# EL_SCH.net
KiCad netlist of a schematic drawn in Altium Designer
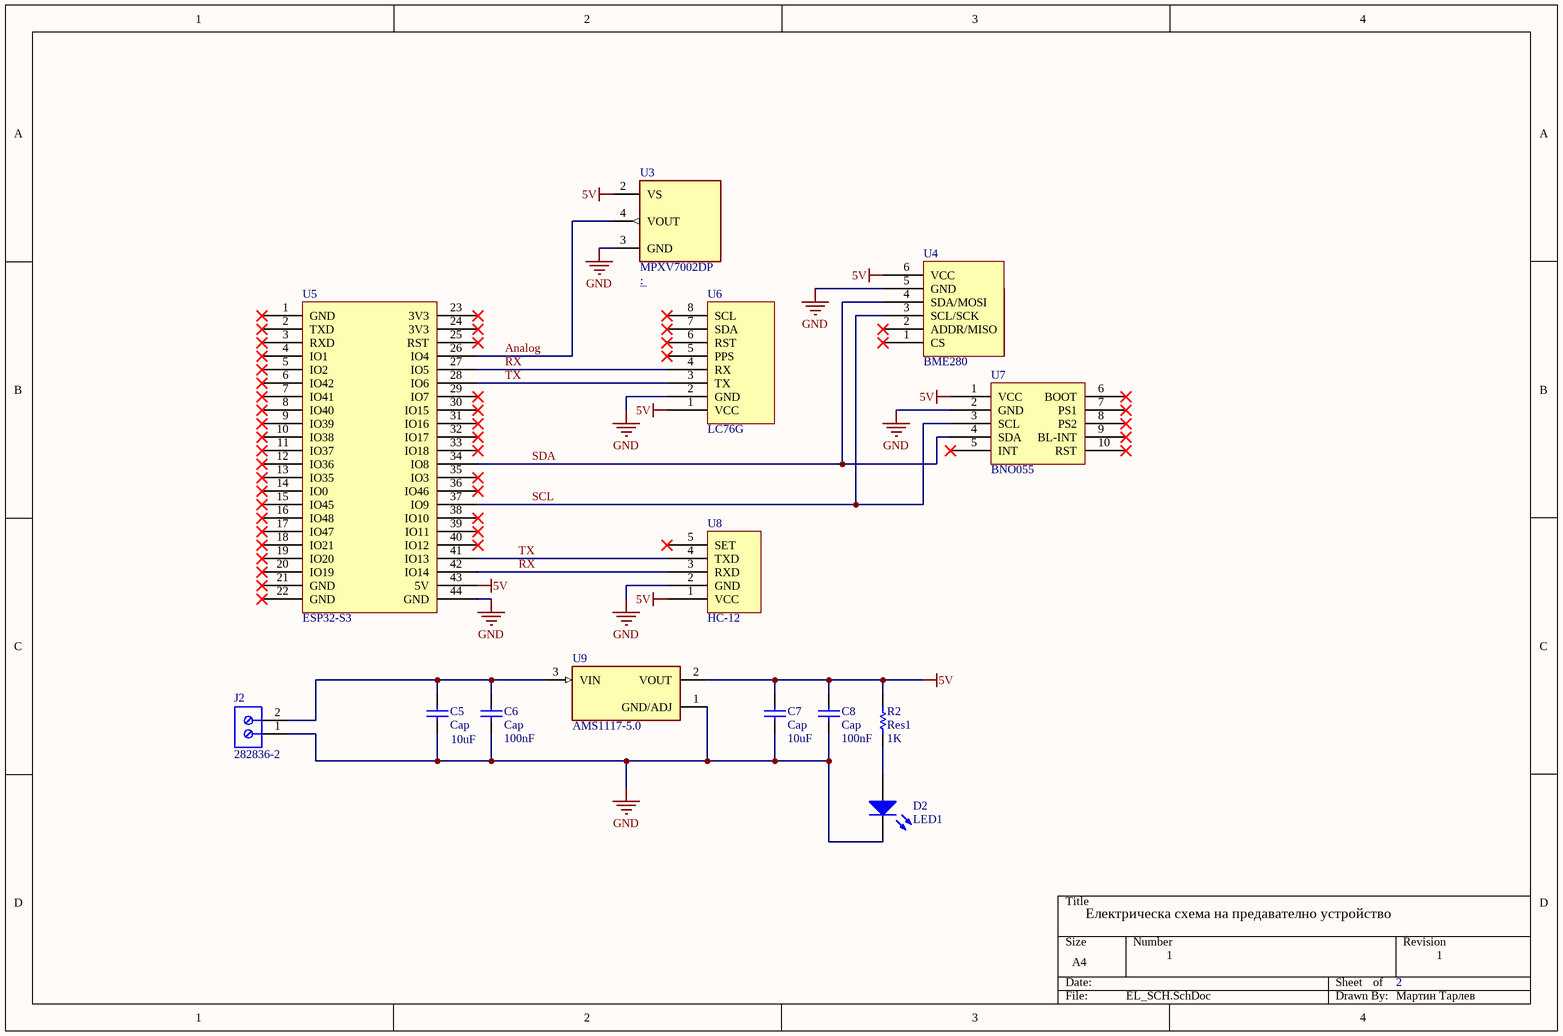
[diagram p0: EL_SCH.SchDoc]

(export (version "E")
  (design (tool "Eeschema 10.0.6"))
  (components
    (comp (ref "C5")
      (value "Cap")
      (footprint "CAP2")
      (description "Capacitor")
      (fields (field (name "ALTIUM_VALUE") "10uF") (field (name "PUBLISHER") "Altium Limited"))
      (libsource (lib "Miscellaneous Devices") (part "Cap"))
    )
    (comp (ref "C6")
      (value "Cap")
      (footprint "CON")
      (description "Capacitor")
      (fields (field (name "ALTIUM_VALUE") "100nF") (field (name "PUBLISHER") "Altium Limited"))
      (libsource (lib "Miscellaneous Devices") (part "Cap"))
    )
    (comp (ref "C7")
      (value "Cap")
      (footprint "CAP2")
      (description "Capacitor")
      (fields (field (name "ALTIUM_VALUE") "10uF") (field (name "PUBLISHER") "Altium Limited"))
      (libsource (lib "Miscellaneous Devices") (part "Cap"))
    )
    (comp (ref "C8")
      (value "Cap")
      (footprint "CON")
      (description "Capacitor")
      (fields (field (name "ALTIUM_VALUE") "100nF") (field (name "PUBLISHER") "Altium Limited"))
      (libsource (lib "Miscellaneous Devices") (part "Cap"))
    )
    (comp (ref "D2")
      (value "LED1")
      (footprint "LED-1")
      (description "Typical RED GaAs LED")
      (fields (field (name "PUBLISHER") "Altium Limited"))
      (libsource (lib "Miscellaneous Devices") (part "LED1"))
    )
    (comp (ref "J2")
      (value "282836-2")
      (footprint "TECO-282836-2_V")
      (description "Female Header, Pitch 5 mm, 1 x 2 Position, Height 10 mm, Tail Length 3.5 mm, Rohs, Bulk")
      (fields (field (name "VOLTAGE") "300V") (field (name "MANUFACTURER") "TE Connectivity"))
      (libsource (lib "Altium Content Vault") (part "CN-1P-F-TB2"))
    )
    (comp (ref "R2")
      (value "Res1")
      (footprint "AXIAL-0.3")
      (description "Resistor")
      (fields (field (name "ALTIUM_VALUE") "1K") (field (name "PUBLISHER") "Altium Limited"))
      (libsource (lib "Miscellaneous Devices") (part "Res1"))
    )
    (comp (ref "U3")
      (value "MPXV7002DP")
      (footprint "XDCR_MPXV7002DP")
      (fields (field (name "MF") "NXP USA"))
      (libsource (lib "MPXV7002DP") (part "MPXV7002DP"))
    )
    (comp (ref "U4") (value "BME280") (libsource (lib "First_PCB_dip") (part "BME280")))
    (comp (ref "U5") (value "ESP32-S3") (libsource (lib "First_PCB_dip") (part "ESP32-S3")))
    (comp (ref "U6") (value "LC76G") (libsource (lib "First_PCB_dip") (part "LC76G")))
    (comp (ref "U7") (value "BNO055") (libsource (lib "First_PCB_dip") (part "BNO055")))
    (comp (ref "U8") (value "HC-12") (libsource (lib "First_PCB_dip") (part "HC-12")))
    (comp (ref "U9")
      (value "AMS1117-5.0")
      (footprint "SOT229P700X180-4N")
      (description "1A LOW DROPOUT VOLTAGE REGULATOR")
      (fields (field (name "MF") "ams"))
      (libsource (lib "AMS1117-5.0") (part "AMS1117-5.0"))
    )
  )
  (nets
    (net (code "1") (name "/Analog") (class "Default")
      (node (ref "U3") (pin "4") (pinfunction "VOUT_4") (pintype "output"))
      (node (ref "U5") (pin "26") (pinfunction "IO4_26") (pintype "passive"))
    )
    (net (code "2") (name "/RX") (class "Default")
      (node (ref "U5") (pin "27") (pinfunction "IO5_27") (pintype "passive"))
      (node (ref "U5") (pin "42") (pinfunction "IO14_42") (pintype "passive"))
      (node (ref "U6") (pin "4") (pinfunction "RX_4") (pintype "passive"))
      (node (ref "U8") (pin "3") (pinfunction "RXD_3") (pintype "passive"))
    )
    (net (code "3") (name "/SCL") (class "Default")
      (node (ref "U4") (pin "3") (pinfunction "SCL/SCK_3") (pintype "passive"))
      (node (ref "U5") (pin "37") (pinfunction "IO9_37") (pintype "passive"))
      (node (ref "U7") (pin "3") (pinfunction "SCL_3") (pintype "passive"))
    )
    (net (code "4") (name "/SDA") (class "Default")
      (node (ref "U4") (pin "4") (pinfunction "SDA/MOSI_4") (pintype "passive"))
      (node (ref "U5") (pin "34") (pinfunction "IO8_34") (pintype "passive"))
      (node (ref "U7") (pin "4") (pinfunction "SDA_4") (pintype "passive"))
    )
    (net (code "5") (name "/TX") (class "Default")
      (node (ref "U5") (pin "28") (pinfunction "IO6_28") (pintype "passive"))
      (node (ref "U5") (pin "41") (pinfunction "IO13_41") (pintype "passive"))
      (node (ref "U6") (pin "3") (pinfunction "TX_3") (pintype "passive"))
      (node (ref "U8") (pin "4") (pinfunction "TXD_4") (pintype "passive"))
    )
    (net (code "6") (name "5V") (class "Default")
      (node (ref "C7") (pin "2") (pinfunction "2_2") (pintype "passive"))
      (node (ref "C8") (pin "2") (pinfunction "2_2") (pintype "passive"))
      (node (ref "R2") (pin "2") (pinfunction "2_2") (pintype "passive"))
      (node (ref "U3") (pin "2") (pinfunction "VS_2") (pintype "power_in"))
      (node (ref "U4") (pin "6") (pinfunction "VCC_6") (pintype "passive"))
      (node (ref "U5") (pin "43") (pinfunction "5V_43") (pintype "passive"))
      (node (ref "U6") (pin "1") (pinfunction "VCC_1") (pintype "passive"))
      (node (ref "U7") (pin "1") (pinfunction "VCC_1") (pintype "passive"))
      (node (ref "U8") (pin "1") (pinfunction "VCC_1") (pintype "passive"))
      (node (ref "U9") (pin "2") (pinfunction "VOUT_2") (pintype "passive"))
    )
    (net (code "7") (name "GND") (class "Default")
      (node (ref "C5") (pin "1") (pinfunction "1_1") (pintype "passive"))
      (node (ref "C6") (pin "1") (pinfunction "1_1") (pintype "passive"))
      (node (ref "C7") (pin "1") (pinfunction "1_1") (pintype "passive"))
      (node (ref "C8") (pin "1") (pinfunction "1_1") (pintype "passive"))
      (node (ref "D2") (pin "2") (pinfunction "K_2") (pintype "passive"))
      (node (ref "J2") (pin "1") (pinfunction "1_1") (pintype "passive"))
      (node (ref "U3") (pin "3") (pinfunction "GND_3") (pintype "power_in"))
      (node (ref "U4") (pin "5") (pinfunction "GND_5") (pintype "passive"))
      (node (ref "U5") (pin "44") (pinfunction "GND_44") (pintype "passive"))
      (node (ref "U6") (pin "2") (pinfunction "GND_2") (pintype "passive"))
      (node (ref "U7") (pin "2") (pinfunction "GND_2") (pintype "passive"))
      (node (ref "U8") (pin "2") (pinfunction "GND_2") (pintype "passive"))
      (node (ref "U9") (pin "1") (pinfunction "GND/ADJ_1") (pintype "power_in"))
    )
    (net (code "8") (name "Net-(D2-A)") (class "Default")
      (node (ref "D2") (pin "1") (pinfunction "A_1") (pintype "passive"))
      (node (ref "R2") (pin "1") (pinfunction "1_1") (pintype "passive"))
    )
    (net (code "9") (name "Net-(U9-VIN)") (class "Default")
      (node (ref "C5") (pin "2") (pinfunction "2_2") (pintype "passive"))
      (node (ref "C6") (pin "2") (pinfunction "2_2") (pintype "passive"))
      (node (ref "J2") (pin "2") (pinfunction "2_2") (pintype "passive"))
      (node (ref "U9") (pin "3") (pinfunction "VIN_3") (pintype "input"))
    )
    (net (code "10") (name "unconnected-(U4-ADDR{slash}MISO-Pad2)") (class "Default")
      (node (ref "U4") (pin "2") (pinfunction "ADDR/MISO_2") (pintype "passive+no_connect"))
    )
    (net (code "11") (name "unconnected-(U4-CS-Pad1)") (class "Default")
      (node (ref "U4") (pin "1") (pinfunction "CS_1") (pintype "passive+no_connect"))
    )
    (net (code "12") (name "unconnected-(U5-3V3-Pad23)") (class "Default")
      (node (ref "U5") (pin "23") (pinfunction "3V3_23") (pintype "passive+no_connect"))
    )
    (net (code "13") (name "unconnected-(U5-3V3-Pad24)") (class "Default")
      (node (ref "U5") (pin "24") (pinfunction "3V3_24") (pintype "passive+no_connect"))
    )
    (net (code "14") (name "unconnected-(U5-GND-Pad1)") (class "Default")
      (node (ref "U5") (pin "1") (pinfunction "GND_1") (pintype "passive+no_connect"))
    )
    (net (code "15") (name "unconnected-(U5-GND-Pad21)") (class "Default")
      (node (ref "U5") (pin "21") (pinfunction "GND_21") (pintype "passive+no_connect"))
    )
    (net (code "16") (name "unconnected-(U5-GND-Pad22)") (class "Default")
      (node (ref "U5") (pin "22") (pinfunction "GND_22") (pintype "passive+no_connect"))
    )
    (net (code "17") (name "unconnected-(U5-IO0-Pad14)") (class "Default")
      (node (ref "U5") (pin "14") (pinfunction "IO0_14") (pintype "passive+no_connect"))
    )
    (net (code "18") (name "unconnected-(U5-IO1-Pad4)") (class "Default")
      (node (ref "U5") (pin "4") (pinfunction "IO1_4") (pintype "passive+no_connect"))
    )
    (net (code "19") (name "unconnected-(U5-IO2-Pad5)") (class "Default")
      (node (ref "U5") (pin "5") (pinfunction "IO2_5") (pintype "passive+no_connect"))
    )
    (net (code "20") (name "unconnected-(U5-IO3-Pad35)") (class "Default")
      (node (ref "U5") (pin "35") (pinfunction "IO3_35") (pintype "passive+no_connect"))
    )
    (net (code "21") (name "unconnected-(U5-IO7-Pad29)") (class "Default")
      (node (ref "U5") (pin "29") (pinfunction "IO7_29") (pintype "passive+no_connect"))
    )
    (net (code "22") (name "unconnected-(U5-IO10-Pad38)") (class "Default")
      (node (ref "U5") (pin "38") (pinfunction "IO10_38") (pintype "passive+no_connect"))
    )
    (net (code "23") (name "unconnected-(U5-IO11-Pad39)") (class "Default")
      (node (ref "U5") (pin "39") (pinfunction "IO11_39") (pintype "passive+no_connect"))
    )
    (net (code "24") (name "unconnected-(U5-IO12-Pad40)") (class "Default")
      (node (ref "U5") (pin "40") (pinfunction "IO12_40") (pintype "passive+no_connect"))
    )
    (net (code "25") (name "unconnected-(U5-IO15-Pad30)") (class "Default")
      (node (ref "U5") (pin "30") (pinfunction "IO15_30") (pintype "passive+no_connect"))
    )
    (net (code "26") (name "unconnected-(U5-IO16-Pad31)") (class "Default")
      (node (ref "U5") (pin "31") (pinfunction "IO16_31") (pintype "passive+no_connect"))
    )
    (net (code "27") (name "unconnected-(U5-IO17-Pad32)") (class "Default")
      (node (ref "U5") (pin "32") (pinfunction "IO17_32") (pintype "passive+no_connect"))
    )
    (net (code "28") (name "unconnected-(U5-IO18-Pad33)") (class "Default")
      (node (ref "U5") (pin "33") (pinfunction "IO18_33") (pintype "passive+no_connect"))
    )
    (net (code "29") (name "unconnected-(U5-IO19-Pad20)") (class "Default")
      (node (ref "U5") (pin "20") (pinfunction "IO19_20") (pintype "passive+no_connect"))
    )
    (net (code "30") (name "unconnected-(U5-IO20-Pad19)") (class "Default")
      (node (ref "U5") (pin "19") (pinfunction "IO20_19") (pintype "passive+no_connect"))
    )
    (net (code "31") (name "unconnected-(U5-IO21-Pad18)") (class "Default")
      (node (ref "U5") (pin "18") (pinfunction "IO21_18") (pintype "passive+no_connect"))
    )
    (net (code "32") (name "unconnected-(U5-IO35-Pad13)") (class "Default")
      (node (ref "U5") (pin "13") (pinfunction "IO35_13") (pintype "passive+no_connect"))
    )
    (net (code "33") (name "unconnected-(U5-IO36-Pad12)") (class "Default")
      (node (ref "U5") (pin "12") (pinfunction "IO36_12") (pintype "passive+no_connect"))
    )
    (net (code "34") (name "unconnected-(U5-IO37-Pad11)") (class "Default")
      (node (ref "U5") (pin "11") (pinfunction "IO37_11") (pintype "passive+no_connect"))
    )
    (net (code "35") (name "unconnected-(U5-IO38-Pad10)") (class "Default")
      (node (ref "U5") (pin "10") (pinfunction "IO38_10") (pintype "passive+no_connect"))
    )
    (net (code "36") (name "unconnected-(U5-IO39-Pad9)") (class "Default")
      (node (ref "U5") (pin "9") (pinfunction "IO39_9") (pintype "passive+no_connect"))
    )
    (net (code "37") (name "unconnected-(U5-IO40-Pad8)") (class "Default")
      (node (ref "U5") (pin "8") (pinfunction "IO40_8") (pintype "passive+no_connect"))
    )
    (net (code "38") (name "unconnected-(U5-IO41-Pad7)") (class "Default")
      (node (ref "U5") (pin "7") (pinfunction "IO41_7") (pintype "passive+no_connect"))
    )
    (net (code "39") (name "unconnected-(U5-IO42-Pad6)") (class "Default")
      (node (ref "U5") (pin "6") (pinfunction "IO42_6") (pintype "passive+no_connect"))
    )
    (net (code "40") (name "unconnected-(U5-IO45-Pad15)") (class "Default")
      (node (ref "U5") (pin "15") (pinfunction "IO45_15") (pintype "passive+no_connect"))
    )
    (net (code "41") (name "unconnected-(U5-IO46-Pad36)") (class "Default")
      (node (ref "U5") (pin "36") (pinfunction "IO46_36") (pintype "passive+no_connect"))
    )
    (net (code "42") (name "unconnected-(U5-IO47-Pad17)") (class "Default")
      (node (ref "U5") (pin "17") (pinfunction "IO47_17") (pintype "passive+no_connect"))
    )
    (net (code "43") (name "unconnected-(U5-IO48-Pad16)") (class "Default")
      (node (ref "U5") (pin "16") (pinfunction "IO48_16") (pintype "passive+no_connect"))
    )
    (net (code "44") (name "unconnected-(U5-RST-Pad25)") (class "Default")
      (node (ref "U5") (pin "25") (pinfunction "RST_25") (pintype "passive+no_connect"))
    )
    (net (code "45") (name "unconnected-(U5-RXD-Pad3)") (class "Default")
      (node (ref "U5") (pin "3") (pinfunction "RXD_3") (pintype "passive+no_connect"))
    )
    (net (code "46") (name "unconnected-(U5-TXD-Pad2)") (class "Default")
      (node (ref "U5") (pin "2") (pinfunction "TXD_2") (pintype "passive+no_connect"))
    )
    (net (code "47") (name "unconnected-(U6-PPS-Pad5)") (class "Default")
      (node (ref "U6") (pin "5") (pinfunction "PPS_5") (pintype "passive+no_connect"))
    )
    (net (code "48") (name "unconnected-(U6-RST-Pad6)") (class "Default")
      (node (ref "U6") (pin "6") (pinfunction "RST_6") (pintype "passive+no_connect"))
    )
    (net (code "49") (name "unconnected-(U6-SCL-Pad8)") (class "Default")
      (node (ref "U6") (pin "8") (pinfunction "SCL_8") (pintype "passive+no_connect"))
    )
    (net (code "50") (name "unconnected-(U6-SDA-Pad7)") (class "Default")
      (node (ref "U6") (pin "7") (pinfunction "SDA_7") (pintype "passive+no_connect"))
    )
    (net (code "51") (name "unconnected-(U7-BL-INT-Pad9)") (class "Default")
      (node (ref "U7") (pin "9") (pinfunction "BL-INT_9") (pintype "passive+no_connect"))
    )
    (net (code "52") (name "unconnected-(U7-BOOT-Pad6)") (class "Default")
      (node (ref "U7") (pin "6") (pinfunction "BOOT_6") (pintype "passive+no_connect"))
    )
    (net (code "53") (name "unconnected-(U7-INT-Pad5)") (class "Default")
      (node (ref "U7") (pin "5") (pinfunction "INT_5") (pintype "passive+no_connect"))
    )
    (net (code "54") (name "unconnected-(U7-PS1-Pad7)") (class "Default")
      (node (ref "U7") (pin "7") (pinfunction "PS1_7") (pintype "passive+no_connect"))
    )
    (net (code "55") (name "unconnected-(U7-PS2-Pad8)") (class "Default")
      (node (ref "U7") (pin "8") (pinfunction "PS2_8") (pintype "passive+no_connect"))
    )
    (net (code "56") (name "unconnected-(U7-RST-Pad10)") (class "Default")
      (node (ref "U7") (pin "10") (pinfunction "RST_10") (pintype "passive+no_connect"))
    )
    (net (code "57") (name "unconnected-(U8-SET-Pad5)") (class "Default")
      (node (ref "U8") (pin "5") (pinfunction "SET_5") (pintype "passive+no_connect"))
    )
  )
)
